# ProPrj_LED__2025-12-06-20-17-04.net
KiCad netlist of a schematic drawn in EasyEDA Pro
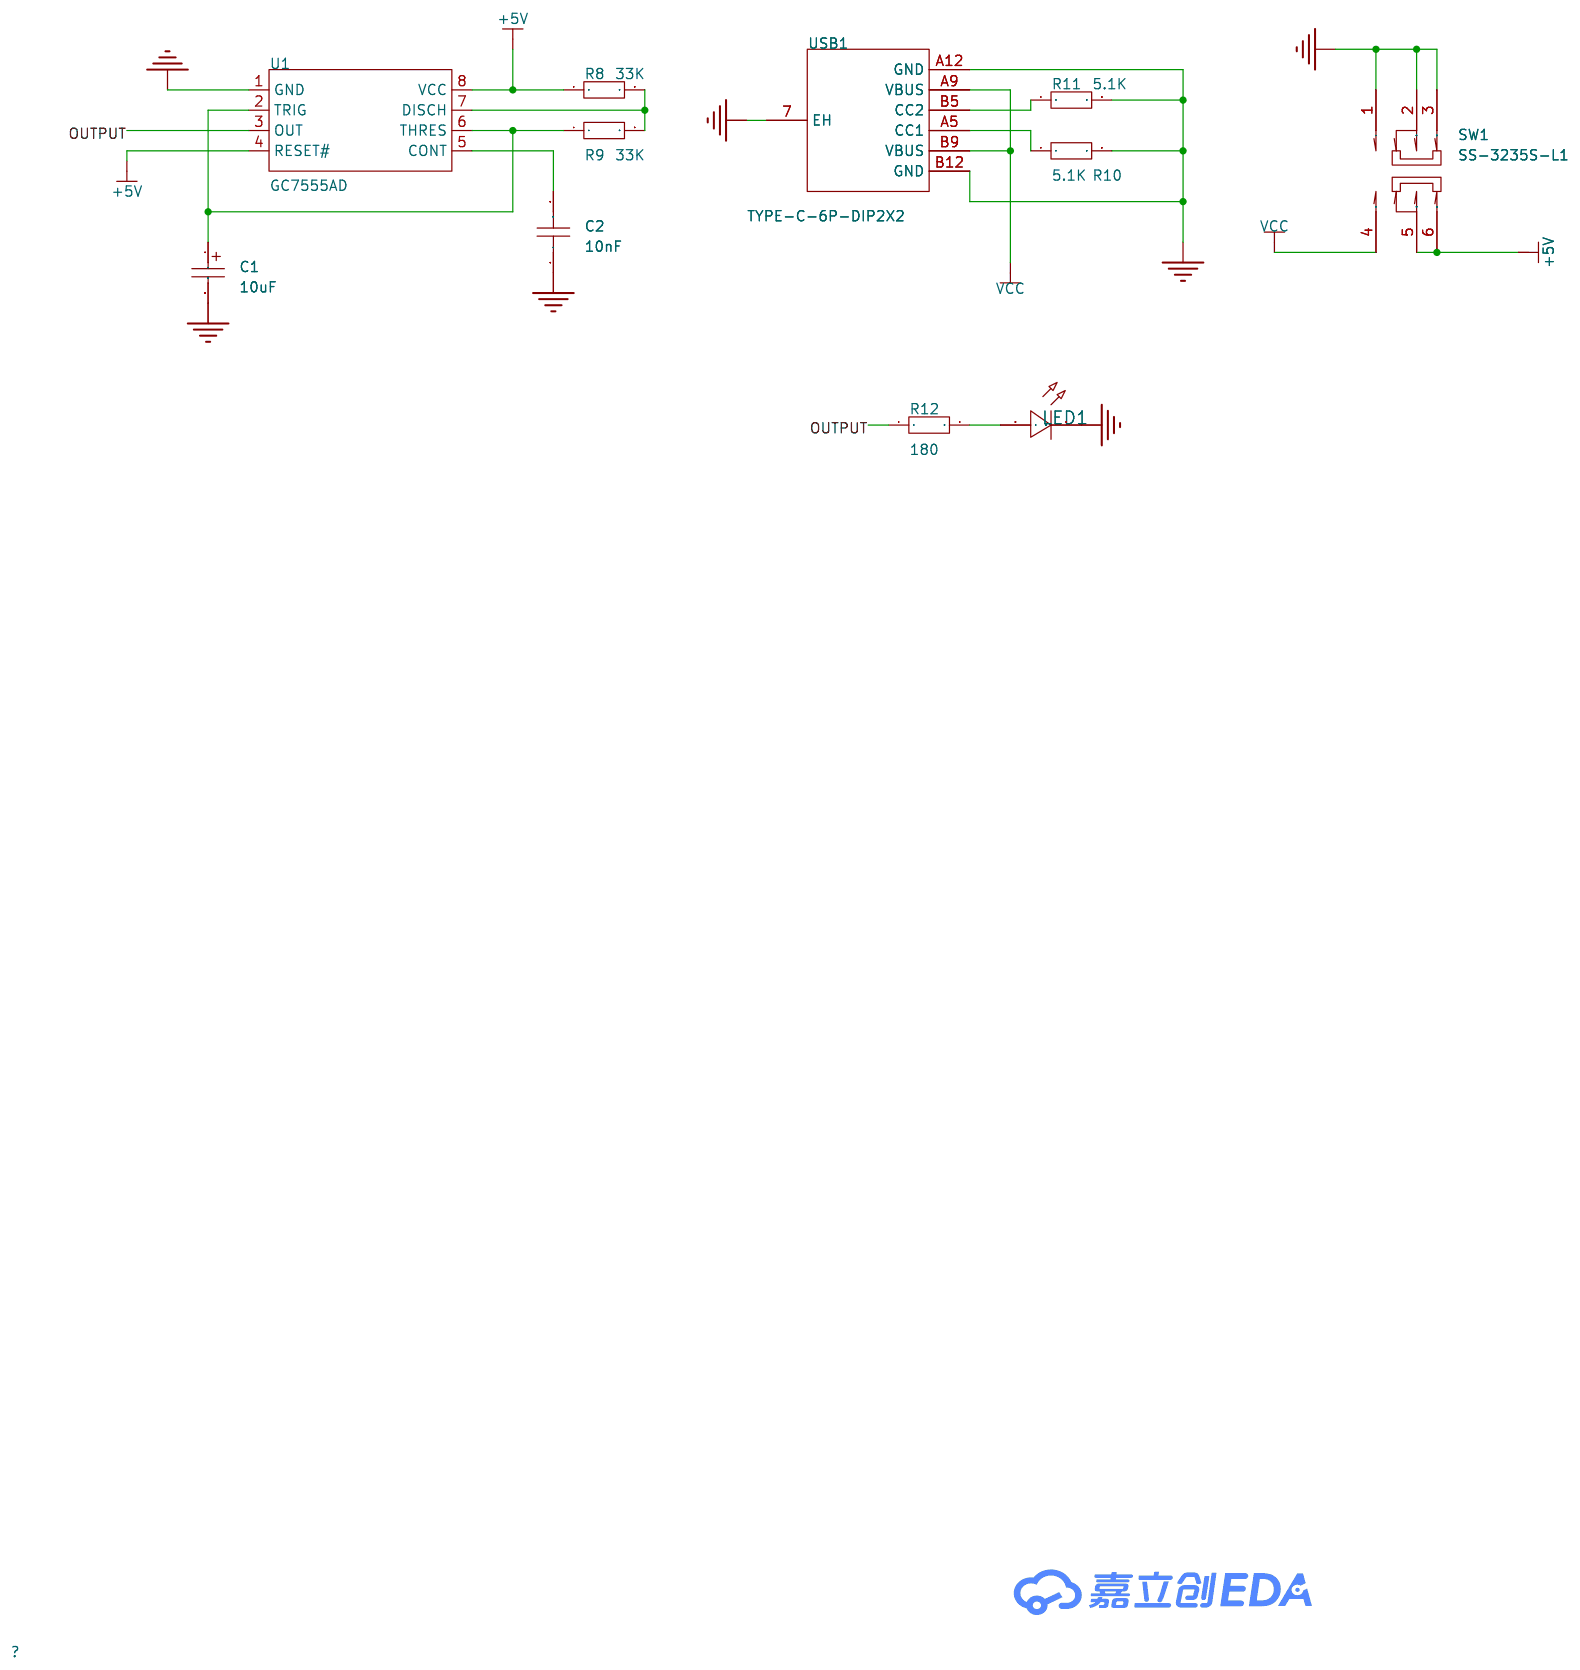
[diagram p0: schematic sheet]

(export (version "E")
  (design (tool "Eeschema 10.0.6"))
  (components
    (comp (ref "C1")
      (value "10uF")
      (footprint "easyedapro:C_Ele_SMD_3x5.4mm")
      (libsource (lib "easyedapro") (part "CAP"))
    )
    (comp (ref "C2")
      (value "10nF")
      (footprint "easyedapro:C0603")
      (libsource (lib "easyedapro") (part "Capacitance"))
    )
    (comp (ref "LED1")
      (value "~")
      (footprint "easyedapro:LED_0603")
      (libsource (lib "easyedapro") (part "LED_R"))
    )
    (comp (ref "R8") (value "33K") (footprint "easyedapro:R0805") (libsource (lib "easyedapro") (part "电阻")))
    (comp (ref "R9") (value "33K") (footprint "easyedapro:R0805") (libsource (lib "easyedapro") (part "电阻")))
    (comp (ref "R10")
      (value "5.1K")
      (footprint "easyedapro:R0805")
      (libsource (lib "easyedapro") (part "电阻"))
    )
    (comp (ref "R11")
      (value "5.1K")
      (footprint "easyedapro:R0805")
      (libsource (lib "easyedapro") (part "电阻"))
    )
    (comp (ref "R12") (value "180") (footprint "easyedapro:R0805") (libsource (lib "easyedapro") (part "电阻")))
    (comp (ref "SW1")
      (value "SS-3235S-L1")
      (footprint "easyedapro:SW-SMD_SS-3235S-LX")
      (description "电路结构:双刀双掷;安装方式:卧贴;开关颜色:黑色;额定电流:50mA;额定电压:12V;工作寿命:1万次;")
      (fields (field (name "Manufacturer") "XKB Connection(中国星坤)"))
      (libsource (lib "easyedapro") (part "SS-3235S-L1"))
    )
    (comp (ref "U1")
      (value "GC7555AD")
      (footprint "easyedapro:PDIP-8_L9.5-W6.4-P2.54-LS7.6-BL")
      (description "通用计时器：时基电路；计时；脉冲产生；满足用户（至少工业级）自主可控的需求。")
      (fields (field (name "Manufacturer") "Sungine(双竞集成)"))
      (libsource (lib "easyedapro") (part "GC7555AD"))
    )
    (comp (ref "USB1")
      (value "TYPE-C-6P-DIP2X2")
      (footprint "easyedapro:TYPE-C-SMD_TYPE-C-6P")
      (libsource (lib "easyedapro") (part "TYPE-C-6P-DIP2X2"))
    )
  )
  (nets
    (net (code "1") (name "+5V") (class "Default")
      (node (ref "R8") (pin "1") (pinfunction "1_1") (pintype "input"))
      (node (ref "SW1") (pin "5") (pinfunction "5_5") (pintype "unspecified"))
      (node (ref "SW1") (pin "6") (pinfunction "6_6") (pintype "unspecified"))
      (node (ref "U1") (pin "4") (pinfunction "RESET#_4") (pintype "unspecified"))
      (node (ref "U1") (pin "8") (pinfunction "VCC_8") (pintype "unspecified"))
    )
    (net (code "2") (name "/OUTPUT") (class "Default")
      (node (ref "R12") (pin "1") (pinfunction "1_1") (pintype "input"))
      (node (ref "U1") (pin "3") (pinfunction "OUT_3") (pintype "unspecified"))
    )
    (net (code "3") (name "GND") (class "Default")
      (node (ref "C1") (pin "2") (pinfunction "2_2") (pintype "input"))
      (node (ref "C2") (pin "1") (pinfunction "1_1") (pintype "input"))
      (node (ref "LED1") (pin "1") (pinfunction "C_1") (pintype "input"))
      (node (ref "R10") (pin "2") (pinfunction "2_2") (pintype "input"))
      (node (ref "R11") (pin "2") (pinfunction "2_2") (pintype "input"))
      (node (ref "SW1") (pin "1") (pinfunction "1_1") (pintype "unspecified"))
      (node (ref "SW1") (pin "2") (pinfunction "2_2") (pintype "unspecified"))
      (node (ref "SW1") (pin "3") (pinfunction "3_3") (pintype "unspecified"))
      (node (ref "U1") (pin "1") (pinfunction "GND_1") (pintype "unspecified"))
      (node (ref "USB1") (pin "7") (pinfunction "EH_7") (pintype "unspecified"))
      (node (ref "USB1") (pin "A12") (pinfunction "GND_A12") (pintype "unspecified"))
      (node (ref "USB1") (pin "B12") (pinfunction "GND_B12") (pintype "unspecified"))
    )
    (net (code "4") (name "Net-(LED1-A)") (class "Default")
      (node (ref "LED1") (pin "2") (pinfunction "A_2") (pintype "input"))
      (node (ref "R12") (pin "2") (pinfunction "2_2") (pintype "input"))
    )
    (net (code "5") (name "Net-(U1-CONT)") (class "Default")
      (node (ref "C2") (pin "2") (pinfunction "2_2") (pintype "input"))
      (node (ref "U1") (pin "5") (pinfunction "CONT_5") (pintype "unspecified"))
    )
    (net (code "6") (name "Net-(U1-DISCH)") (class "Default")
      (node (ref "R8") (pin "2") (pinfunction "2_2") (pintype "input"))
      (node (ref "R9") (pin "2") (pinfunction "2_2") (pintype "input"))
      (node (ref "U1") (pin "7") (pinfunction "DISCH_7") (pintype "unspecified"))
    )
    (net (code "7") (name "Net-(U1-THRES)") (class "Default")
      (node (ref "C1") (pin "1") (pinfunction "1_1") (pintype "input"))
      (node (ref "R9") (pin "1") (pinfunction "1_1") (pintype "input"))
      (node (ref "U1") (pin "2") (pinfunction "TRIG_2") (pintype "unspecified"))
      (node (ref "U1") (pin "6") (pinfunction "THRES_6") (pintype "unspecified"))
    )
    (net (code "8") (name "Net-(USB1-CC1)") (class "Default")
      (node (ref "R10") (pin "1") (pinfunction "1_1") (pintype "input"))
      (node (ref "USB1") (pin "A5") (pinfunction "CC1_A5") (pintype "unspecified"))
    )
    (net (code "9") (name "Net-(USB1-CC2)") (class "Default")
      (node (ref "R11") (pin "1") (pinfunction "1_1") (pintype "input"))
      (node (ref "USB1") (pin "B5") (pinfunction "CC2_B5") (pintype "unspecified"))
    )
    (net (code "10") (name "VCC") (class "Default")
      (node (ref "SW1") (pin "4") (pinfunction "4_4") (pintype "unspecified"))
      (node (ref "USB1") (pin "A9") (pinfunction "VBUS_A9") (pintype "unspecified"))
      (node (ref "USB1") (pin "B9") (pinfunction "VBUS_B9") (pintype "unspecified"))
    )
  )
)
